# QSTL_MicroDSUB_Plug_FFC.net
KiCad netlist of a schematic drawn in Altium Designer
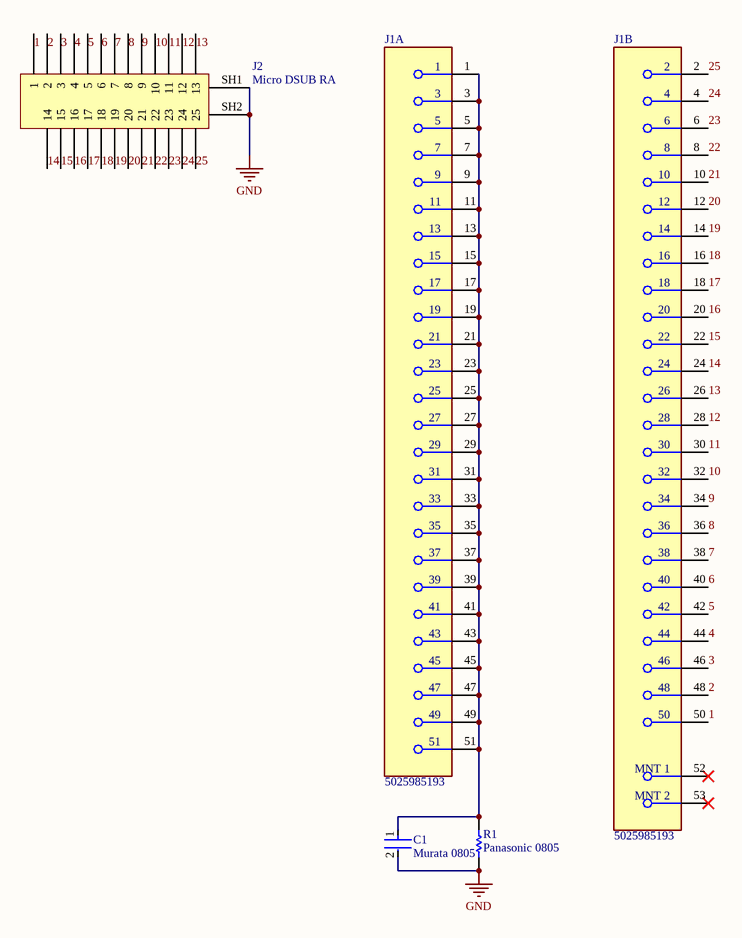
[diagram p0: QSTL_MicroDSUB_Plug_FFC.SchDoc]

(export (version "E")
  (design (tool "Eeschema 10.0.6"))
  (components
    (comp (ref "C1")
      (value "Murata 0805")
      (footprint "FP-GRM21B-0_15-MFG")
      (description "Chip Multilayer Ceramic Capacitors for General Purpose, 0805, 10uF, X7R, 15%, 10%, 10V")
      (fields (field (name "TOLERANCE") "10%"))
      (libsource (lib "Altium Content Vault") (part "b4654b650e69147ec39a6b967a45e02"))
    )
    (comp (ref "J1")
      (value "5025985193")
      (footprint "FP-5025985193-MFG")
      (description "CONN FPC 51POS 0.30MM R/A")
      (fields
        (field (name "OCTOPART") "https://octopart.com/502598-5193-molex-33127991")
        (field (name "MANUFACTURER") "Molex")
      )
      (libsource (lib "Altium Content Vault") (part "2f3a718b51213836fa913b7fc1fd98d"))
    )
    (comp (ref "J2")
      (value "Micro DSUB RA")
      (footprint "581-M25-113L461")
      (description "https://www.digikey.com/en/products/detail/norcomp-inc/581-M25-113L461/13557494")
      (libsource (lib "QSTL_MicroDSUB_Plug_FFC") (part "581-M25-113L461"))
    )
    (comp (ref "R1")
      (value "Panasonic 0805")
      (footprint "RESC2013X60X40LL20T25")
      (fields (field (name "MANUFACTURER") "Panasonic") (field (name "PART NUMBER") "ERA6AEB222V"))
      (libsource (lib "Altium Content Vault") (part "RES"))
    )
  )
  (nets
    (net (code "1") (name "/1") (class "Default")
      (node (ref "J1") (pin "50") (pinfunction "50_50") (pintype "passive"))
      (node (ref "J2") (pin "1") (pinfunction "1_1") (pintype "passive"))
    )
    (net (code "2") (name "/2") (class "Default")
      (node (ref "J1") (pin "48") (pinfunction "48_48") (pintype "passive"))
      (node (ref "J2") (pin "2") (pinfunction "2_2") (pintype "passive"))
    )
    (net (code "3") (name "/3") (class "Default")
      (node (ref "J1") (pin "46") (pinfunction "46_46") (pintype "passive"))
      (node (ref "J2") (pin "3") (pinfunction "3_3") (pintype "passive"))
    )
    (net (code "4") (name "/4") (class "Default")
      (node (ref "J1") (pin "44") (pinfunction "44_44") (pintype "passive"))
      (node (ref "J2") (pin "4") (pinfunction "4_4") (pintype "passive"))
    )
    (net (code "5") (name "/5") (class "Default")
      (node (ref "J1") (pin "42") (pinfunction "42_42") (pintype "passive"))
      (node (ref "J2") (pin "5") (pinfunction "5_5") (pintype "passive"))
    )
    (net (code "6") (name "/6") (class "Default")
      (node (ref "J1") (pin "40") (pinfunction "40_40") (pintype "passive"))
      (node (ref "J2") (pin "6") (pinfunction "6_6") (pintype "passive"))
    )
    (net (code "7") (name "/7") (class "Default")
      (node (ref "J1") (pin "38") (pinfunction "38_38") (pintype "passive"))
      (node (ref "J2") (pin "7") (pinfunction "7_7") (pintype "passive"))
    )
    (net (code "8") (name "/8") (class "Default")
      (node (ref "J1") (pin "36") (pinfunction "36_36") (pintype "passive"))
      (node (ref "J2") (pin "8") (pinfunction "8_8") (pintype "passive"))
    )
    (net (code "9") (name "/9") (class "Default")
      (node (ref "J1") (pin "34") (pinfunction "34_34") (pintype "passive"))
      (node (ref "J2") (pin "9") (pinfunction "9_9") (pintype "passive"))
    )
    (net (code "10") (name "/10") (class "Default")
      (node (ref "J1") (pin "32") (pinfunction "32_32") (pintype "passive"))
      (node (ref "J2") (pin "10") (pinfunction "10_10") (pintype "passive"))
    )
    (net (code "11") (name "/11") (class "Default")
      (node (ref "J1") (pin "30") (pinfunction "30_30") (pintype "passive"))
      (node (ref "J2") (pin "11") (pinfunction "11_11") (pintype "passive"))
    )
    (net (code "12") (name "/12") (class "Default")
      (node (ref "J1") (pin "28") (pinfunction "28_28") (pintype "passive"))
      (node (ref "J2") (pin "12") (pinfunction "12_12") (pintype "passive"))
    )
    (net (code "13") (name "/13") (class "Default")
      (node (ref "J1") (pin "26") (pinfunction "26_26") (pintype "passive"))
      (node (ref "J2") (pin "13") (pinfunction "13_13") (pintype "passive"))
    )
    (net (code "14") (name "/14") (class "Default")
      (node (ref "J1") (pin "24") (pinfunction "24_24") (pintype "passive"))
      (node (ref "J2") (pin "14") (pinfunction "14_14") (pintype "passive"))
    )
    (net (code "15") (name "/15") (class "Default")
      (node (ref "J1") (pin "22") (pinfunction "22_22") (pintype "passive"))
      (node (ref "J2") (pin "15") (pinfunction "15_15") (pintype "passive"))
    )
    (net (code "16") (name "/16") (class "Default")
      (node (ref "J1") (pin "20") (pinfunction "20_20") (pintype "passive"))
      (node (ref "J2") (pin "16") (pinfunction "16_16") (pintype "passive"))
    )
    (net (code "17") (name "/17") (class "Default")
      (node (ref "J1") (pin "18") (pinfunction "18_18") (pintype "passive"))
      (node (ref "J2") (pin "17") (pinfunction "17_17") (pintype "passive"))
    )
    (net (code "18") (name "/18") (class "Default")
      (node (ref "J1") (pin "16") (pinfunction "16_16") (pintype "passive"))
      (node (ref "J2") (pin "18") (pinfunction "18_18") (pintype "passive"))
    )
    (net (code "19") (name "/19") (class "Default")
      (node (ref "J1") (pin "14") (pinfunction "14_14") (pintype "passive"))
      (node (ref "J2") (pin "19") (pinfunction "19_19") (pintype "passive"))
    )
    (net (code "20") (name "/20") (class "Default")
      (node (ref "J1") (pin "12") (pinfunction "12_12") (pintype "passive"))
      (node (ref "J2") (pin "20") (pinfunction "20_20") (pintype "passive"))
    )
    (net (code "21") (name "/21") (class "Default")
      (node (ref "J1") (pin "10") (pinfunction "10_10") (pintype "passive"))
      (node (ref "J2") (pin "21") (pinfunction "21_21") (pintype "passive"))
    )
    (net (code "22") (name "/22") (class "Default")
      (node (ref "J1") (pin "8") (pinfunction "8_8") (pintype "passive"))
      (node (ref "J2") (pin "22") (pinfunction "22_22") (pintype "passive"))
    )
    (net (code "23") (name "/23") (class "Default")
      (node (ref "J1") (pin "6") (pinfunction "6_6") (pintype "passive"))
      (node (ref "J2") (pin "23") (pinfunction "23_23") (pintype "passive"))
    )
    (net (code "24") (name "/24") (class "Default")
      (node (ref "J1") (pin "4") (pinfunction "4_4") (pintype "passive"))
      (node (ref "J2") (pin "24") (pinfunction "24_24") (pintype "passive"))
    )
    (net (code "25") (name "/25") (class "Default")
      (node (ref "J1") (pin "2") (pinfunction "2_2") (pintype "passive"))
      (node (ref "J2") (pin "25") (pinfunction "25_25") (pintype "passive"))
    )
    (net (code "26") (name "GND") (class "Default")
      (node (ref "C1") (pin "2") (pinfunction "2_2") (pintype "passive"))
      (node (ref "J2") (pin "SH1") (pinfunction "SH1_SH1") (pintype "passive"))
      (node (ref "J2") (pin "SH2") (pinfunction "SH2_SH2") (pintype "passive"))
      (node (ref "R1") (pin "2") (pinfunction "2_2") (pintype "passive"))
    )
    (net (code "27") (name "Net-(C1-Pad1)") (class "Default")
      (node (ref "C1") (pin "1") (pinfunction "1_1") (pintype "passive"))
      (node (ref "J1") (pin "1") (pinfunction "1_1") (pintype "passive"))
      (node (ref "J1") (pin "11") (pinfunction "11_11") (pintype "passive"))
      (node (ref "J1") (pin "13") (pinfunction "13_13") (pintype "passive"))
      (node (ref "J1") (pin "15") (pinfunction "15_15") (pintype "passive"))
      (node (ref "J1") (pin "17") (pinfunction "17_17") (pintype "passive"))
      (node (ref "J1") (pin "19") (pinfunction "19_19") (pintype "passive"))
      (node (ref "J1") (pin "21") (pinfunction "21_21") (pintype "passive"))
      (node (ref "J1") (pin "23") (pinfunction "23_23") (pintype "passive"))
      (node (ref "J1") (pin "25") (pinfunction "25_25") (pintype "passive"))
      (node (ref "J1") (pin "27") (pinfunction "27_27") (pintype "passive"))
      (node (ref "J1") (pin "29") (pinfunction "29_29") (pintype "passive"))
      (node (ref "J1") (pin "3") (pinfunction "3_3") (pintype "passive"))
      (node (ref "J1") (pin "31") (pinfunction "31_31") (pintype "passive"))
      (node (ref "J1") (pin "33") (pinfunction "33_33") (pintype "passive"))
      (node (ref "J1") (pin "35") (pinfunction "35_35") (pintype "passive"))
      (node (ref "J1") (pin "37") (pinfunction "37_37") (pintype "passive"))
      (node (ref "J1") (pin "39") (pinfunction "39_39") (pintype "passive"))
      (node (ref "J1") (pin "41") (pinfunction "41_41") (pintype "passive"))
      (node (ref "J1") (pin "43") (pinfunction "43_43") (pintype "passive"))
      (node (ref "J1") (pin "45") (pinfunction "45_45") (pintype "passive"))
      (node (ref "J1") (pin "47") (pinfunction "47_47") (pintype "passive"))
      (node (ref "J1") (pin "49") (pinfunction "49_49") (pintype "passive"))
      (node (ref "J1") (pin "5") (pinfunction "5_5") (pintype "passive"))
      (node (ref "J1") (pin "51") (pinfunction "51_51") (pintype "passive"))
      (node (ref "J1") (pin "7") (pinfunction "7_7") (pintype "passive"))
      (node (ref "J1") (pin "9") (pinfunction "9_9") (pintype "passive"))
      (node (ref "R1") (pin "1") (pinfunction "1_1") (pintype "passive"))
    )
    (net (code "28") (name "unconnected-(J1B-MNT_1-Pad52)") (class "Default")
      (node (ref "J1") (pin "52") (pinfunction "MNT_1_52") (pintype "passive+no_connect"))
    )
    (net (code "29") (name "unconnected-(J1B-MNT_2-Pad53)") (class "Default")
      (node (ref "J1") (pin "53") (pinfunction "MNT_2_53") (pintype "passive+no_connect"))
    )
  )
)
